# Solar-Charger-Board.net
KiCad netlist of a schematic drawn in EAGLE
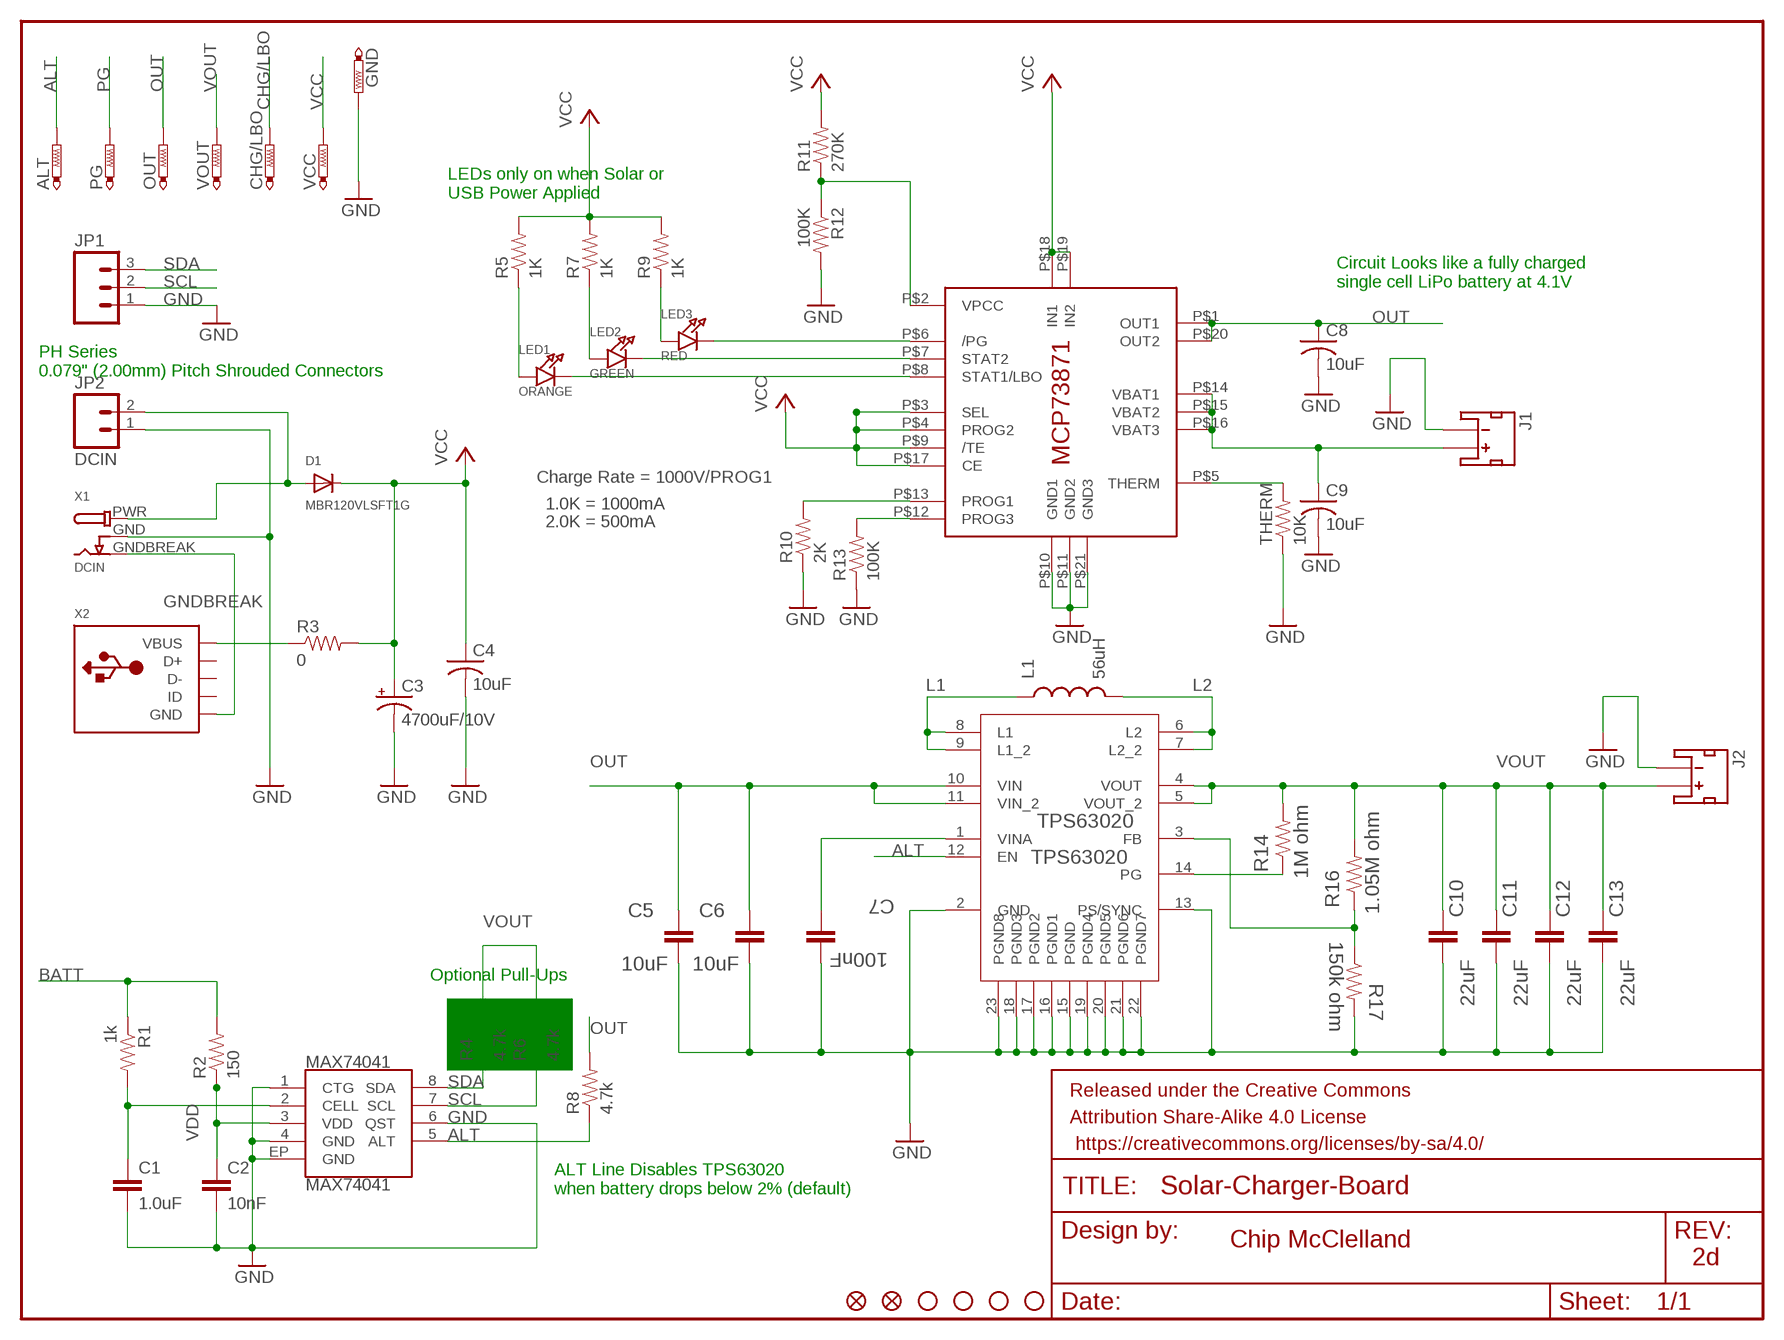
[diagram p0: schematic, sheet 1]

(export (version "E")
  (design (tool "Eeschema 10.0.6"))
  (components
    (comp (ref "ALT")
      (value "PTR1TP09R")
      (footprint "eagle-import:TP09R")
      (libsource (lib "eagle-import") (part "PTR1TP09R"))
    )
    (comp (ref "C1")
      (value "1.0uF")
      (footprint "eagle-import:0805")
      (libsource (lib "eagle-import") (part "1.0UF-25V-+80/-20(0805)"))
    )
    (comp (ref "C2")
      (value "10nF")
      (footprint "eagle-import:0805")
      (libsource (lib "eagle-import") (part "2.2UF-25V-+80/-20(0805)"))
    )
    (comp (ref "C3")
      (value "4700uF/10V")
      (footprint "eagle-import:E5-13")
      (libsource (lib "eagle-import") (part "CPOL-USE5-13"))
    )
    (comp (ref "C4")
      (value "10uF")
      (footprint "eagle-import:C0805K")
      (libsource (lib "eagle-import") (part "C-USC0805K"))
    )
    (comp (ref "C5")
      (value "10uF")
      (footprint "eagle-import:0805")
      (libsource (lib "eagle-import") (part "CAP0805"))
    )
    (comp (ref "C6")
      (value "10uF")
      (footprint "eagle-import:0805")
      (libsource (lib "eagle-import") (part "CAP0805"))
    )
    (comp (ref "C7")
      (value "100nF")
      (footprint "eagle-import:0805")
      (libsource (lib "eagle-import") (part "CAP0805"))
    )
    (comp (ref "C8")
      (value "10uF")
      (footprint "eagle-import:C0805K")
      (libsource (lib "eagle-import") (part "C-USC0805K"))
    )
    (comp (ref "C9")
      (value "10uF")
      (footprint "eagle-import:C0805K")
      (libsource (lib "eagle-import") (part "C-USC0805K"))
    )
    (comp (ref "C10")
      (value "22uF")
      (footprint "eagle-import:0805")
      (libsource (lib "eagle-import") (part "CAP0805"))
    )
    (comp (ref "C11")
      (value "22uF")
      (footprint "eagle-import:0805")
      (libsource (lib "eagle-import") (part "CAP0805"))
    )
    (comp (ref "C12")
      (value "22uF")
      (footprint "eagle-import:0805")
      (libsource (lib "eagle-import") (part "CAP0805"))
    )
    (comp (ref "C13")
      (value "22uF")
      (footprint "eagle-import:0805")
      (libsource (lib "eagle-import") (part "CAP0805"))
    )
    (comp (ref "CHG/LBO")
      (value "PTR1TP09R")
      (footprint "eagle-import:TP09R")
      (libsource (lib "eagle-import") (part "PTR1TP09R"))
    )
    (comp (ref "D1")
      (value "MBR120VLSFT1G")
      (footprint "eagle-import:SOD-123")
      (libsource (lib "eagle-import") (part "DIODESOD-123"))
    )
    (comp (ref "FID1")
      (value "FIDUCIALUFIDUCIAL")
      (footprint "eagle-import:MICRO-FIDUCIAL")
      (libsource (lib "eagle-import") (part "FIDUCIALUFIDUCIAL"))
    )
    (comp (ref "FID2")
      (value "FIDUCIALUFIDUCIAL")
      (footprint "eagle-import:MICRO-FIDUCIAL")
      (libsource (lib "eagle-import") (part "FIDUCIALUFIDUCIAL"))
    )
    (comp (ref "FRAME1")
      (value "FRAME-LETTER")
      (footprint "eagle-import:CREATIVE_COMMONS")
      (libsource (lib "eagle-import") (part "FRAME-LETTER"))
    )
    (comp (ref "GND")
      (value "PTR1TP09R")
      (footprint "eagle-import:TP09R")
      (libsource (lib "eagle-import") (part "PTR1TP09R"))
    )
    (comp (ref "J1")
      (value "JST_2MM_MALE")
      (footprint "eagle-import:JST-2-SMD")
      (libsource (lib "eagle-import") (part "JST_2MM_MALE"))
    )
    (comp (ref "J2")
      (value "JST_2MM_MALE")
      (footprint "eagle-import:JST-2-SMD")
      (libsource (lib "eagle-import") (part "JST_2MM_MALE"))
    )
    (comp (ref "JP1")
      (value "M03LOCK")
      (footprint "eagle-import:1X03_LOCK")
      (libsource (lib "eagle-import") (part "M03LOCK"))
    )
    (comp (ref "JP2")
      (value "DCIN")
      (footprint "eagle-import:1X02_LOCK")
      (libsource (lib "eagle-import") (part "M02LOCK"))
    )
    (comp (ref "JP3")
      (value "STAND-OFF")
      (footprint "eagle-import:STAND-OFF")
      (libsource (lib "eagle-import") (part "STAND-OFF"))
    )
    (comp (ref "JP4")
      (value "STAND-OFF")
      (footprint "eagle-import:STAND-OFF")
      (libsource (lib "eagle-import") (part "STAND-OFF"))
    )
    (comp (ref "JP5")
      (value "STAND-OFF")
      (footprint "eagle-import:STAND-OFF")
      (libsource (lib "eagle-import") (part "STAND-OFF"))
    )
    (comp (ref "JP6")
      (value "STAND-OFF")
      (footprint "eagle-import:STAND-OFF")
      (libsource (lib "eagle-import") (part "STAND-OFF"))
    )
    (comp (ref "L1")
      (value "56uH")
      (footprint "eagle-import:SDR0403")
      (libsource (lib "eagle-import") (part "INDUCTORSDR0403-560KL"))
    )
    (comp (ref "LED1")
      (value "ORANGE")
      (footprint "eagle-import:CHIPLED_0805_NOOUTLINE")
      (libsource (lib "eagle-import") (part "LED0805_NOOUTLINE"))
    )
    (comp (ref "LED2")
      (value "GREEN")
      (footprint "eagle-import:CHIPLED_0805_NOOUTLINE")
      (libsource (lib "eagle-import") (part "LED0805_NOOUTLINE"))
    )
    (comp (ref "LED3")
      (value "RED")
      (footprint "eagle-import:CHIPLED_0805_NOOUTLINE")
      (libsource (lib "eagle-import") (part "LED0805_NOOUTLINE"))
    )
    (comp (ref "MAX74041")
      (value "MAX74041")
      (footprint "eagle-import:TDFN-8")
      (libsource (lib "eagle-import") (part "MAX1704X"))
    )
    (comp (ref "MCP73871")
      (value "U1")
      (footprint "eagle-import:QFN20_4MM")
      (libsource (lib "eagle-import") (part "MCP73871"))
    )
    (comp (ref "OUT")
      (value "PTR1TP09R")
      (footprint "eagle-import:TP09R")
      (libsource (lib "eagle-import") (part "PTR1TP09R"))
    )
    (comp (ref "PG")
      (value "PTR1TP09R")
      (footprint "eagle-import:TP09R")
      (libsource (lib "eagle-import") (part "PTR1TP09R"))
    )
    (comp (ref "R1")
      (value "1k")
      (footprint "eagle-import:0805")
      (libsource (lib "eagle-import") (part "RESISTOR0805-RES"))
    )
    (comp (ref "R2")
      (value "150")
      (footprint "eagle-import:0805")
      (libsource (lib "eagle-import") (part "RESISTOR0805-RES"))
    )
    (comp (ref "R3")
      (value "0")
      (footprint "eagle-import:0805")
      (libsource (lib "eagle-import") (part "RESISTOR0805-RES"))
    )
    (comp (ref "R4")
      (value "4.7k")
      (footprint "eagle-import:0805")
      (libsource (lib "eagle-import") (part "RESISTOR0805-RES"))
    )
    (comp (ref "R5")
      (value "1K")
      (footprint "eagle-import:0805")
      (libsource (lib "eagle-import") (part "RESISTOR0805-RES"))
    )
    (comp (ref "R6")
      (value "4.7k")
      (footprint "eagle-import:0805")
      (libsource (lib "eagle-import") (part "RESISTOR0805-RES"))
    )
    (comp (ref "R7")
      (value "1K")
      (footprint "eagle-import:0805")
      (libsource (lib "eagle-import") (part "RESISTOR0805-RES"))
    )
    (comp (ref "R8")
      (value "4.7k")
      (footprint "eagle-import:0805")
      (libsource (lib "eagle-import") (part "RESISTOR0805-RES"))
    )
    (comp (ref "R9")
      (value "1K")
      (footprint "eagle-import:0805")
      (libsource (lib "eagle-import") (part "RESISTOR0805-RES"))
    )
    (comp (ref "R10")
      (value "2K")
      (footprint "eagle-import:0805")
      (libsource (lib "eagle-import") (part "RESISTOR0805-RES"))
    )
    (comp (ref "R11")
      (value "270K")
      (footprint "eagle-import:0805")
      (libsource (lib "eagle-import") (part "RESISTOR0805-RES"))
    )
    (comp (ref "R12")
      (value "100K")
      (footprint "eagle-import:0805")
      (libsource (lib "eagle-import") (part "RESISTOR0805-RES"))
    )
    (comp (ref "R13")
      (value "100K")
      (footprint "eagle-import:0805")
      (libsource (lib "eagle-import") (part "RESISTOR0805-RES"))
    )
    (comp (ref "R14")
      (value "1M ohm")
      (footprint "eagle-import:0805")
      (libsource (lib "eagle-import") (part "RESISTOR0805-RES"))
    )
    (comp (ref "R16")
      (value "1.05M ohm")
      (footprint "eagle-import:0805")
      (libsource (lib "eagle-import") (part "RESISTOR0805-RES"))
    )
    (comp (ref "R17")
      (value "150k ohm")
      (footprint "eagle-import:0805")
      (libsource (lib "eagle-import") (part "RESISTOR0805-RES"))
    )
    (comp (ref "THERM")
      (value "10K")
      (footprint "eagle-import:0805")
      (libsource (lib "eagle-import") (part "RESISTOR0805-RES"))
    )
    (comp (ref "TPS63020")
      (value "TPS63020")
      (footprint "eagle-import:QFN14-3X4MM")
      (libsource (lib "eagle-import") (part "TPS63020"))
    )
    (comp (ref "VCC")
      (value "PTR1TP09R")
      (footprint "eagle-import:TP09R")
      (libsource (lib "eagle-import") (part "PTR1TP09R"))
    )
    (comp (ref "VOUT")
      (value "PTR1TP09R")
      (footprint "eagle-import:TP09R")
      (libsource (lib "eagle-import") (part "PTR1TP09R"))
    )
    (comp (ref "X1")
      (value "DCIN")
      (footprint "eagle-import:DCJACK_2MM_SMT")
      (libsource (lib "eagle-import") (part "DCBARRELSMT"))
    )
    (comp (ref "X2")
      (value "USBMINIBLARGE")
      (footprint "eagle-import:USB-MINIB_LARGER")
      (libsource (lib "eagle-import") (part "USBMINIBLARGE"))
    )
  )
  (nets
    (net (code "1") (name "/ALT") (class "Default")
      (node (ref "ALT") (pin "TP") (pinfunction "TP_TP") (pintype "input"))
      (node (ref "MAX74041") (pin "5") (pinfunction "ALT_5") (pintype "bidirectional"))
      (node (ref "R8") (pin "1") (pinfunction "1_1") (pintype "passive"))
      (node (ref "TPS63020") (pin "12") (pinfunction "EN_12") (pintype "bidirectional"))
    )
    (net (code "2") (name "/BATT") (class "Default")
      (node (ref "C9") (pin "1") (pinfunction "1_1") (pintype "passive"))
      (node (ref "J1") (pin "2") (pinfunction "+_2") (pintype "bidirectional"))
      (node (ref "MCP73871") (pin "P$14") (pinfunction "VBAT1_P$14") (pintype "output"))
      (node (ref "MCP73871") (pin "P$15") (pinfunction "VBAT2_P$15") (pintype "output"))
      (node (ref "MCP73871") (pin "P$16") (pinfunction "VBAT3_P$16") (pintype "output"))
      (node (ref "R1") (pin "1") (pinfunction "1_1") (pintype "passive"))
      (node (ref "R2") (pin "2") (pinfunction "2_2") (pintype "passive"))
    )
    (net (code "3") (name "/CHG{slash}LBO") (class "Default")
      (node (ref "CHG/LBO") (pin "TP") (pinfunction "TP_TP") (pintype "input"))
      (node (ref "LED1") (pin "C") (pinfunction "C_C") (pintype "passive"))
      (node (ref "MCP73871") (pin "P$8") (pinfunction "STAT1/LBO_P$8") (pintype "output"))
    )
    (net (code "4") (name "/GNDBREAK") (class "Default")
      (node (ref "X1") (pin "GNDBREAK") (pinfunction "GND_GNDBREAK") (pintype "power_in"))
      (node (ref "X2") (pin "GND") (pinfunction "GND_GND") (pintype "power_in"))
      (node (ref "X2") (pin "GND1") (pinfunction "GND_GND1") (pintype "power_in"))
      (node (ref "X2") (pin "GND2") (pinfunction "GND_GND2") (pintype "power_in"))
      (node (ref "X2") (pin "GND3") (pinfunction "GND_GND3") (pintype "power_in"))
      (node (ref "X2") (pin "GND4") (pinfunction "GND_GND4") (pintype "power_in"))
    )
    (net (code "5") (name "/L1") (class "Default")
      (node (ref "L1") (pin "P$1") (pinfunction "1_P$1") (pintype "passive"))
      (node (ref "TPS63020") (pin "8") (pinfunction "L1_8") (pintype "bidirectional"))
      (node (ref "TPS63020") (pin "9") (pinfunction "L1_2_9") (pintype "bidirectional"))
    )
    (net (code "6") (name "/L2") (class "Default")
      (node (ref "L1") (pin "P$2") (pinfunction "2_P$2") (pintype "passive"))
      (node (ref "TPS63020") (pin "6") (pinfunction "L2_6") (pintype "bidirectional"))
      (node (ref "TPS63020") (pin "7") (pinfunction "L2_2_7") (pintype "bidirectional"))
    )
    (net (code "7") (name "/OUT") (class "Default")
      (node (ref "C5") (pin "1") (pinfunction "1_1") (pintype "passive"))
      (node (ref "C6") (pin "1") (pinfunction "1_1") (pintype "passive"))
      (node (ref "C8") (pin "1") (pinfunction "1_1") (pintype "passive"))
      (node (ref "MCP73871") (pin "P$1") (pinfunction "OUT1_P$1") (pintype "output"))
      (node (ref "MCP73871") (pin "P$20") (pinfunction "OUT2_P$20") (pintype "output"))
      (node (ref "OUT") (pin "TP") (pinfunction "TP_TP") (pintype "input"))
      (node (ref "R8") (pin "2") (pinfunction "2_2") (pintype "passive"))
      (node (ref "TPS63020") (pin "10") (pinfunction "VIN_10") (pintype "bidirectional"))
      (node (ref "TPS63020") (pin "11") (pinfunction "VIN_2_11") (pintype "bidirectional"))
    )
    (net (code "8") (name "/PG") (class "Default")
      (node (ref "PG") (pin "TP") (pinfunction "TP_TP") (pintype "input"))
      (node (ref "R14") (pin "1") (pinfunction "1_1") (pintype "passive"))
      (node (ref "TPS63020") (pin "14") (pinfunction "PG_14") (pintype "bidirectional"))
    )
    (net (code "9") (name "/SCL") (class "Default")
      (node (ref "JP1") (pin "2") (pinfunction "2_2") (pintype "passive"))
      (node (ref "MAX74041") (pin "7") (pinfunction "SCL_7") (pintype "bidirectional"))
      (node (ref "R6") (pin "1") (pinfunction "1_1") (pintype "passive"))
    )
    (net (code "10") (name "/SDA") (class "Default")
      (node (ref "JP1") (pin "3") (pinfunction "3_3") (pintype "passive"))
      (node (ref "MAX74041") (pin "8") (pinfunction "SDA_8") (pintype "bidirectional"))
      (node (ref "R4") (pin "1") (pinfunction "1_1") (pintype "passive"))
    )
    (net (code "11") (name "/VDD") (class "Default")
      (node (ref "C2") (pin "1") (pinfunction "1_1") (pintype "passive"))
      (node (ref "MAX74041") (pin "3") (pinfunction "VDD_3") (pintype "bidirectional"))
      (node (ref "R2") (pin "1") (pinfunction "1_1") (pintype "passive"))
    )
    (net (code "12") (name "/VOUT") (class "Default")
      (node (ref "C10") (pin "1") (pinfunction "1_1") (pintype "passive"))
      (node (ref "C11") (pin "1") (pinfunction "1_1") (pintype "passive"))
      (node (ref "C12") (pin "1") (pinfunction "1_1") (pintype "passive"))
      (node (ref "C13") (pin "1") (pinfunction "1_1") (pintype "passive"))
      (node (ref "J2") (pin "2") (pinfunction "+_2") (pintype "bidirectional"))
      (node (ref "R14") (pin "2") (pinfunction "2_2") (pintype "passive"))
      (node (ref "R16") (pin "2") (pinfunction "2_2") (pintype "passive"))
      (node (ref "R4") (pin "2") (pinfunction "2_2") (pintype "passive"))
      (node (ref "R6") (pin "2") (pinfunction "2_2") (pintype "passive"))
      (node (ref "TPS63020") (pin "4") (pinfunction "VOUT_4") (pintype "bidirectional"))
      (node (ref "TPS63020") (pin "5") (pinfunction "VOUT_2_5") (pintype "bidirectional"))
      (node (ref "VOUT") (pin "TP") (pinfunction "TP_TP") (pintype "input"))
    )
    (net (code "13") (name "GND") (class "Default")
      (node (ref "C1") (pin "2") (pinfunction "2_2") (pintype "passive"))
      (node (ref "C10") (pin "2") (pinfunction "2_2") (pintype "passive"))
      (node (ref "C11") (pin "2") (pinfunction "2_2") (pintype "passive"))
      (node (ref "C12") (pin "2") (pinfunction "2_2") (pintype "passive"))
      (node (ref "C13") (pin "2") (pinfunction "2_2") (pintype "passive"))
      (node (ref "C2") (pin "2") (pinfunction "2_2") (pintype "passive"))
      (node (ref "C3") (pin "-") (pinfunction "-_-") (pintype "passive"))
      (node (ref "C4") (pin "2") (pinfunction "2_2") (pintype "passive"))
      (node (ref "C5") (pin "2") (pinfunction "2_2") (pintype "passive"))
      (node (ref "C6") (pin "2") (pinfunction "2_2") (pintype "passive"))
      (node (ref "C7") (pin "2") (pinfunction "2_2") (pintype "passive"))
      (node (ref "C8") (pin "2") (pinfunction "2_2") (pintype "passive"))
      (node (ref "C9") (pin "2") (pinfunction "2_2") (pintype "passive"))
      (node (ref "GND") (pin "TP") (pinfunction "TP_TP") (pintype "input"))
      (node (ref "J1") (pin "1") (pinfunction "-_1") (pintype "bidirectional"))
      (node (ref "J2") (pin "1") (pinfunction "-_1") (pintype "bidirectional"))
      (node (ref "JP1") (pin "1") (pinfunction "1_1") (pintype "passive"))
      (node (ref "JP2") (pin "1") (pinfunction "1_1") (pintype "passive"))
      (node (ref "MAX74041") (pin "1") (pinfunction "CTG_1") (pintype "bidirectional"))
      (node (ref "MAX74041") (pin "4") (pinfunction "GND_4") (pintype "bidirectional"))
      (node (ref "MAX74041") (pin "6") (pinfunction "QST_6") (pintype "bidirectional"))
      (node (ref "MAX74041") (pin "EP") (pinfunction "GND_EP") (pintype "bidirectional"))
      (node (ref "MCP73871") (pin "P$10") (pinfunction "GND1_P$10") (pintype "power_in"))
      (node (ref "MCP73871") (pin "P$11") (pinfunction "GND2_P$11") (pintype "power_in"))
      (node (ref "MCP73871") (pin "P$21") (pinfunction "GND3_P$21") (pintype "power_in"))
      (node (ref "R10") (pin "1") (pinfunction "1_1") (pintype "passive"))
      (node (ref "R12") (pin "2") (pinfunction "2_2") (pintype "passive"))
      (node (ref "R13") (pin "1") (pinfunction "1_1") (pintype "passive"))
      (node (ref "R17") (pin "2") (pinfunction "2_2") (pintype "passive"))
      (node (ref "THERM") (pin "1") (pinfunction "1_1") (pintype "passive"))
      (node (ref "TPS63020") (pin "13") (pinfunction "PS/SYNC_13") (pintype "bidirectional"))
      (node (ref "TPS63020") (pin "15") (pinfunction "PGND_15") (pintype "bidirectional"))
      (node (ref "TPS63020") (pin "16") (pinfunction "PGND1_16") (pintype "bidirectional"))
      (node (ref "TPS63020") (pin "17") (pinfunction "PGND2_17") (pintype "bidirectional"))
      (node (ref "TPS63020") (pin "18") (pinfunction "PGND3_18") (pintype "bidirectional"))
      (node (ref "TPS63020") (pin "19") (pinfunction "PGND4_19") (pintype "bidirectional"))
      (node (ref "TPS63020") (pin "2") (pinfunction "GND_2") (pintype "bidirectional"))
      (node (ref "TPS63020") (pin "20") (pinfunction "PGND5_20") (pintype "bidirectional"))
      (node (ref "TPS63020") (pin "21") (pinfunction "PGND6_21") (pintype "bidirectional"))
      (node (ref "TPS63020") (pin "22") (pinfunction "PGND7_22") (pintype "bidirectional"))
      (node (ref "TPS63020") (pin "23") (pinfunction "PGND8_23") (pintype "bidirectional"))
      (node (ref "X1") (pin "GND") (pinfunction "GNDBREAK_GND") (pintype "power_in"))
    )
    (net (code "14") (name "Net-(D1-PadA)") (class "Default")
      (node (ref "D1") (pin "A") (pinfunction "A_A") (pintype "passive"))
      (node (ref "JP2") (pin "2") (pinfunction "2_2") (pintype "passive"))
      (node (ref "X1") (pin "PWR") (pinfunction "PWR_PWR") (pintype "power_in"))
    )
    (net (code "15") (name "Net-(LED1-PadA)") (class "Default")
      (node (ref "LED1") (pin "A") (pinfunction "A_A") (pintype "passive"))
      (node (ref "R5") (pin "1") (pinfunction "1_1") (pintype "passive"))
    )
    (net (code "16") (name "Net-(LED2-PadA)") (class "Default")
      (node (ref "LED2") (pin "A") (pinfunction "A_A") (pintype "passive"))
      (node (ref "R7") (pin "1") (pinfunction "1_1") (pintype "passive"))
    )
    (net (code "17") (name "Net-(LED3-PadA)") (class "Default")
      (node (ref "LED3") (pin "A") (pinfunction "A_A") (pintype "passive"))
      (node (ref "R9") (pin "1") (pinfunction "1_1") (pintype "passive"))
    )
    (net (code "18") (name "Net-(MAX74041-CELL)") (class "Default")
      (node (ref "C1") (pin "1") (pinfunction "1_1") (pintype "passive"))
      (node (ref "MAX74041") (pin "2") (pinfunction "CELL_2") (pintype "bidirectional"))
      (node (ref "R1") (pin "2") (pinfunction "2_2") (pintype "passive"))
    )
    (net (code "19") (name "Net-(MCP73871-PROG1)") (class "Default")
      (node (ref "MCP73871") (pin "P$13") (pinfunction "PROG1_P$13") (pintype "input"))
      (node (ref "R10") (pin "2") (pinfunction "2_2") (pintype "passive"))
    )
    (net (code "20") (name "Net-(MCP73871-PROG3)") (class "Default")
      (node (ref "MCP73871") (pin "P$12") (pinfunction "PROG3_P$12") (pintype "input"))
      (node (ref "R13") (pin "2") (pinfunction "2_2") (pintype "passive"))
    )
    (net (code "21") (name "Net-(MCP73871-STAT2)") (class "Default")
      (node (ref "LED2") (pin "C") (pinfunction "C_C") (pintype "passive"))
      (node (ref "MCP73871") (pin "P$7") (pinfunction "STAT2_P$7") (pintype "output"))
    )
    (net (code "22") (name "Net-(MCP73871-THERM)") (class "Default")
      (node (ref "MCP73871") (pin "P$5") (pinfunction "THERM_P$5") (pintype "input"))
      (node (ref "THERM") (pin "2") (pinfunction "2_2") (pintype "passive"))
    )
    (net (code "23") (name "Net-(MCP73871-VPCC)") (class "Default")
      (node (ref "MCP73871") (pin "P$2") (pinfunction "VPCC_P$2") (pintype "input"))
      (node (ref "R11") (pin "1") (pinfunction "1_1") (pintype "passive"))
      (node (ref "R12") (pin "1") (pinfunction "1_1") (pintype "passive"))
    )
    (net (code "24") (name "Net-(MCP73871-{slash}PG)") (class "Default")
      (node (ref "LED3") (pin "C") (pinfunction "C_C") (pintype "passive"))
      (node (ref "MCP73871") (pin "P$6") (pinfunction "/PG_P$6") (pintype "output"))
    )
    (net (code "25") (name "Net-(R3-Pad1)") (class "Default")
      (node (ref "R3") (pin "1") (pinfunction "1_1") (pintype "passive"))
      (node (ref "X2") (pin "VBUS") (pinfunction "VBUS_VBUS") (pintype "power_in"))
    )
    (net (code "26") (name "Net-(TPS63020-FB)") (class "Default")
      (node (ref "R16") (pin "1") (pinfunction "1_1") (pintype "passive"))
      (node (ref "R17") (pin "1") (pinfunction "1_1") (pintype "passive"))
      (node (ref "TPS63020") (pin "3") (pinfunction "FB_3") (pintype "bidirectional"))
    )
    (net (code "27") (name "Net-(TPS63020-VINA)") (class "Default")
      (node (ref "C7") (pin "1") (pinfunction "1_1") (pintype "passive"))
      (node (ref "TPS63020") (pin "1") (pinfunction "VINA_1") (pintype "bidirectional"))
    )
    (net (code "28") (name "VCC") (class "Default")
      (node (ref "C3") (pin "+") (pinfunction "+_+") (pintype "passive"))
      (node (ref "C4") (pin "1") (pinfunction "1_1") (pintype "passive"))
      (node (ref "D1") (pin "C") (pinfunction "C_C") (pintype "passive"))
      (node (ref "MCP73871") (pin "P$17") (pinfunction "CE_P$17") (pintype "input"))
      (node (ref "MCP73871") (pin "P$18") (pinfunction "IN1_P$18") (pintype "input"))
      (node (ref "MCP73871") (pin "P$19") (pinfunction "IN2_P$19") (pintype "input"))
      (node (ref "MCP73871") (pin "P$3") (pinfunction "SEL_P$3") (pintype "input"))
      (node (ref "MCP73871") (pin "P$4") (pinfunction "PROG2_P$4") (pintype "input"))
      (node (ref "MCP73871") (pin "P$9") (pinfunction "/TE_P$9") (pintype "input"))
      (node (ref "R11") (pin "2") (pinfunction "2_2") (pintype "passive"))
      (node (ref "R3") (pin "2") (pinfunction "2_2") (pintype "passive"))
      (node (ref "R5") (pin "2") (pinfunction "2_2") (pintype "passive"))
      (node (ref "R7") (pin "2") (pinfunction "2_2") (pintype "passive"))
      (node (ref "R9") (pin "2") (pinfunction "2_2") (pintype "passive"))
      (node (ref "VCC") (pin "TP") (pinfunction "TP_TP") (pintype "input"))
    )
    (net (code "29") (name "unconnected-(J1-PAD1-PadNC1)") (class "Default")
      (node (ref "J1") (pin "NC1") (pinfunction "PAD1_NC1") (pintype "bidirectional"))
    )
    (net (code "30") (name "unconnected-(J1-PAD2-PadNC2)") (class "Default")
      (node (ref "J1") (pin "NC2") (pinfunction "PAD2_NC2") (pintype "bidirectional"))
    )
    (net (code "31") (name "unconnected-(J2-PAD1-PadNC1)") (class "Default")
      (node (ref "J2") (pin "NC1") (pinfunction "PAD1_NC1") (pintype "bidirectional"))
    )
    (net (code "32") (name "unconnected-(J2-PAD2-PadNC2)") (class "Default")
      (node (ref "J2") (pin "NC2") (pinfunction "PAD2_NC2") (pintype "bidirectional"))
    )
    (net (code "33") (name "unconnected-(X2-PadD+)") (class "Default")
      (node (ref "X2") (pin "D+") (pinfunction "D+_D+") (pintype "bidirectional"))
    )
    (net (code "34") (name "unconnected-(X2-PadD-)") (class "Default")
      (node (ref "X2") (pin "D-") (pinfunction "D-_D-") (pintype "bidirectional"))
    )
    (net (code "35") (name "unconnected-(X2-PadID)") (class "Default")
      (node (ref "X2") (pin "ID") (pinfunction "ID_ID") (pintype "bidirectional"))
    )
  )
)
